# SCH_FC-ESP32_2026-02-12.net
KiCad netlist of a schematic drawn in EasyEDA
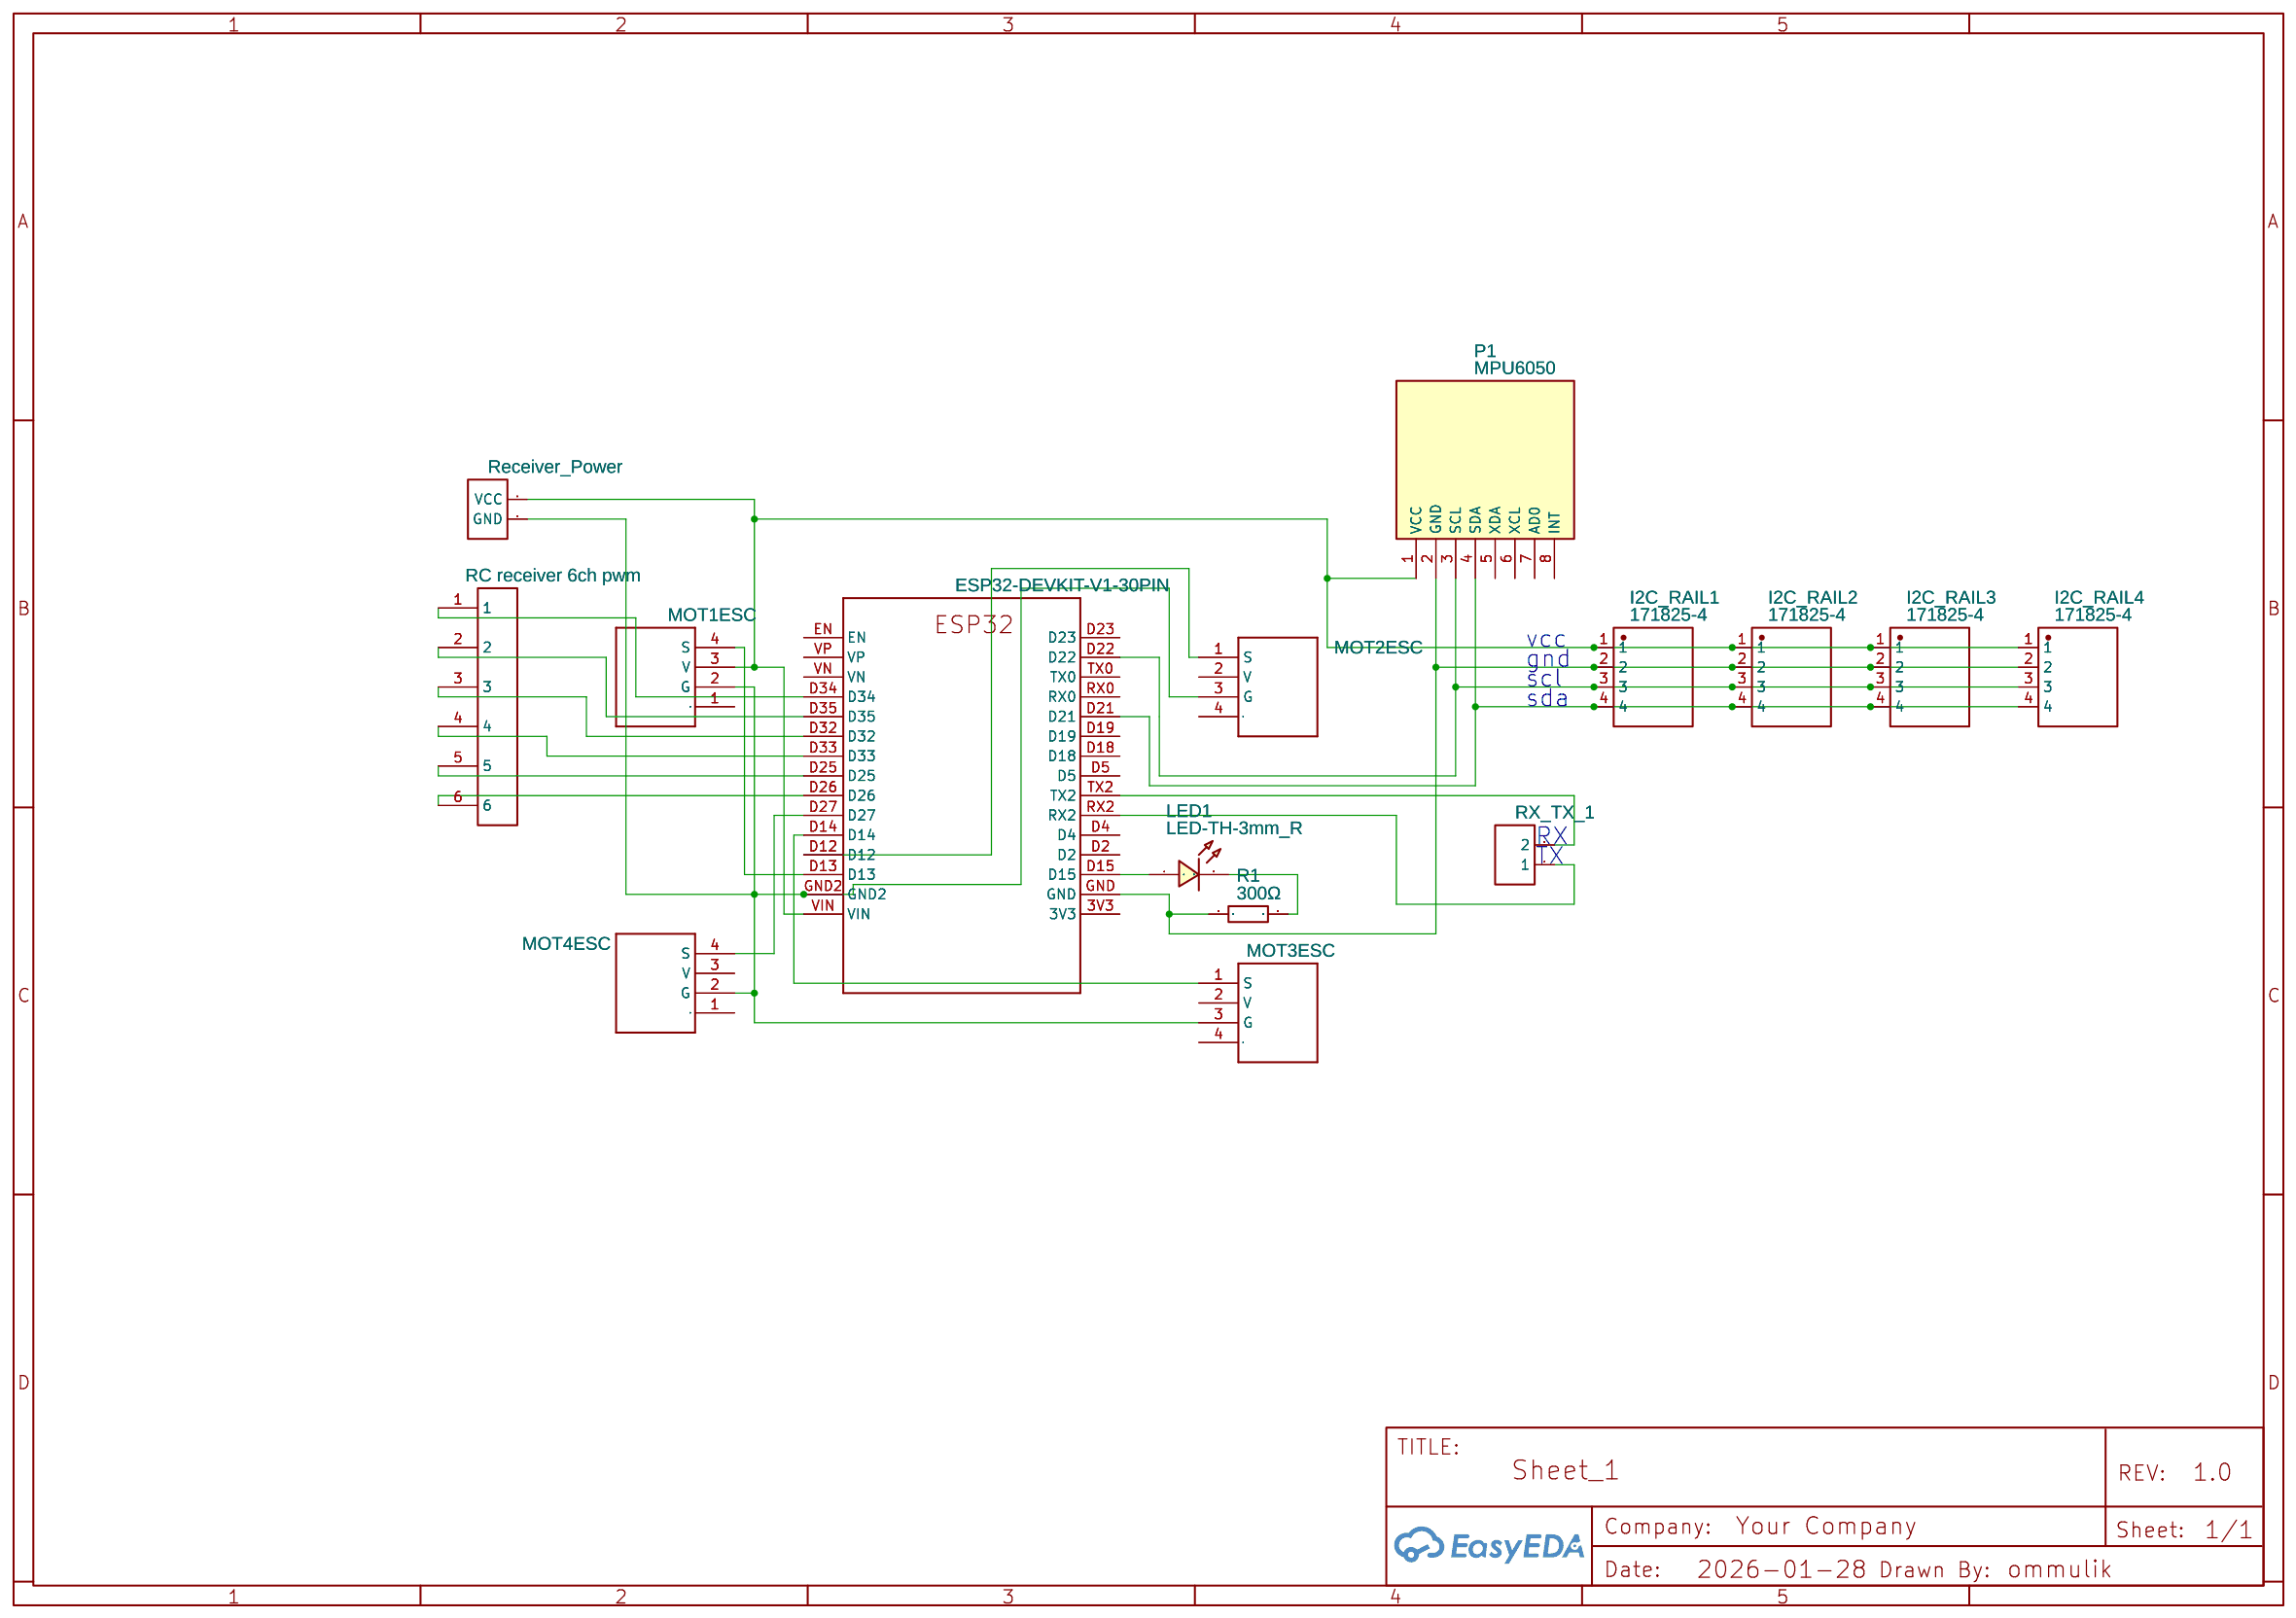
[diagram p0: schematic sheet]

(export (version "E")
  (design (tool "Eeschema 10.0.6"))
  (components
    (comp (ref "2") (value "ESP32-DEVKIT-V1-30PIN") (libsource (lib "") (part "ESP32-DEVKIT-V1-30PIN")))
    (comp (ref "H1") (value "Receiver_Power") (libsource (lib "") (part "HDR-F-2.54_1x2_1")))
    (comp (ref "H2") (value "RX_TX_1") (libsource (lib "") (part "HDR-F-2.54_1x2")))
    (comp (ref "I2C_RAIL1")
      (value "171825-4")
      (fields (field (name "Manufacturer") "TE Connectivity(泰科电子)"))
      (libsource (lib "") (part "171825-4"))
    )
    (comp (ref "I2C_RAIL2")
      (value "171825-4")
      (fields (field (name "Manufacturer") "TE Connectivity(泰科电子)"))
      (libsource (lib "") (part "171825-4"))
    )
    (comp (ref "I2C_RAIL3")
      (value "171825-4")
      (fields (field (name "Manufacturer") "TE Connectivity(泰科电子)"))
      (libsource (lib "") (part "171825-4"))
    )
    (comp (ref "I2C_RAIL4")
      (value "171825-4")
      (fields (field (name "Manufacturer") "TE Connectivity(泰科电子)"))
      (libsource (lib "") (part "171825-4"))
    )
    (comp (ref "J1") (value "MOT4ESC") (libsource (lib "") (part "bluepill_scsi-rescue_171825-4-171825-4")))
    (comp (ref "J2") (value "MOT1ESC") (libsource (lib "") (part "bluepill_scsi-rescue_171825-4-171825-4")))
    (comp (ref "J3") (value "MOT2ESC") (libsource (lib "") (part "bluepill_scsi-rescue_171825-4-171825-4_1")))
    (comp (ref "J4") (value "MOT3ESC") (libsource (lib "") (part "bluepill_scsi-rescue_171825-4-171825-4_1")))
    (comp (ref "LED1")
      (value "LED-TH-3mm_R")
      (fields
        (field (name "Manufacturer Part") "204-10SDRD/S530-A3-L")
        (field (name "Manufacturer") "EVERLIGHT(台湾亿光)")
      )
      (libsource (lib "") (part "LED-TH-3mm_R"))
    )
    (comp (ref "P1") (value "MPU6050") (libsource (lib "") (part "MPU6050")))
    (comp (ref "R1")
      (value "300Ω")
      (fields
        (field (name "Manufacturer Part") "CF1/4W-330KΩ±5% T52")
        (field (name "Manufacturer") "CCO(千志电子)")
      )
      (libsource (lib "") (part "CF1/4W-330KΩ±5% T52"))
    )
    (comp (ref "S2") (value "RC receiver 6ch pwm") (libsource (lib "") (part "6PIN_BERG")))
  )
  (nets
    (net (code "1") (name "Net-(2-PadD15)") (class "Default")
      (node (ref "2") (pin "D15") (pinfunction "D15_D15") (pintype "unspecified"))
      (node (ref "LED1") (pin "1") (pinfunction "1_1") (pintype "unspecified"))
    )
    (net (code "2") (name "Net-(2-PadD25)") (class "Default")
      (node (ref "2") (pin "D25") (pinfunction "D25_D25") (pintype "unspecified"))
      (node (ref "S2") (pin "5") (pinfunction "5_5") (pintype "unspecified"))
    )
    (net (code "3") (name "Net-(2-PadD26)") (class "Default")
      (node (ref "2") (pin "D26") (pinfunction "D26_D26") (pintype "unspecified"))
      (node (ref "S2") (pin "6") (pinfunction "6_6") (pintype "unspecified"))
    )
    (net (code "4") (name "Net-(2-PadD32)") (class "Default")
      (node (ref "2") (pin "D32") (pinfunction "D32_D32") (pintype "unspecified"))
      (node (ref "S2") (pin "3") (pinfunction "3_3") (pintype "unspecified"))
    )
    (net (code "5") (name "Net-(2-PadD33)") (class "Default")
      (node (ref "2") (pin "D33") (pinfunction "D33_D33") (pintype "unspecified"))
      (node (ref "S2") (pin "4") (pinfunction "4_4") (pintype "unspecified"))
    )
    (net (code "6") (name "Net-(2-PadD34)") (class "Default")
      (node (ref "2") (pin "D34") (pinfunction "D34_D34") (pintype "unspecified"))
      (node (ref "S2") (pin "1") (pinfunction "1_1") (pintype "unspecified"))
    )
    (net (code "7") (name "Net-(2-PadD35)") (class "Default")
      (node (ref "2") (pin "D35") (pinfunction "D35_D35") (pintype "unspecified"))
      (node (ref "S2") (pin "2") (pinfunction "2_2") (pintype "unspecified"))
    )
    (net (code "8") (name "Net-(2-PadRX2)") (class "Default")
      (node (ref "2") (pin "RX2") (pinfunction "RX2_RX2") (pintype "unspecified"))
      (node (ref "H2") (pin "1") (pinfunction "1_1") (pintype "input"))
    )
    (net (code "9") (name "Net-(2-PadTX2)") (class "Default")
      (node (ref "2") (pin "TX2") (pinfunction "TX2_TX2") (pintype "unspecified"))
      (node (ref "H2") (pin "2") (pinfunction "2_2") (pintype "input"))
    )
    (net (code "10") (name "Net-(H1-GND)") (class "Default")
      (node (ref "2") (pin "GND2") (pinfunction "GND2_GND2") (pintype "unspecified"))
      (node (ref "H1") (pin "1") (pinfunction "GND_1") (pintype "input"))
      (node (ref "J1") (pin "2") (pinfunction "G_2") (pintype "unspecified"))
      (node (ref "J2") (pin "2") (pinfunction "G_2") (pintype "unspecified"))
      (node (ref "J3") (pin "3") (pinfunction "G_3") (pintype "unspecified"))
      (node (ref "J4") (pin "3") (pinfunction "G_3") (pintype "unspecified"))
    )
    (net (code "11") (name "Net-(H1-VCC)") (class "Default")
      (node (ref "2") (pin "VIN") (pinfunction "VIN_VIN") (pintype "unspecified"))
      (node (ref "H1") (pin "2") (pinfunction "VCC_2") (pintype "input"))
      (node (ref "I2C_RAIL1") (pin "1") (pinfunction "1_1") (pintype "unspecified"))
      (node (ref "I2C_RAIL2") (pin "1") (pinfunction "1_1") (pintype "unspecified"))
      (node (ref "I2C_RAIL3") (pin "1") (pinfunction "1_1") (pintype "unspecified"))
      (node (ref "I2C_RAIL4") (pin "1") (pinfunction "1_1") (pintype "unspecified"))
      (node (ref "J2") (pin "3") (pinfunction "V_3") (pintype "unspecified"))
      (node (ref "P1") (pin "1") (pinfunction "VCC_1") (pintype "unspecified"))
    )
    (net (code "12") (name "Net-(J1-S)") (class "Default")
      (node (ref "2") (pin "D27") (pinfunction "D27_D27") (pintype "unspecified"))
      (node (ref "J1") (pin "4") (pinfunction "S_4") (pintype "unspecified"))
    )
    (net (code "13") (name "Net-(J2-S)") (class "Default")
      (node (ref "2") (pin "D13") (pinfunction "D13_D13") (pintype "unspecified"))
      (node (ref "J2") (pin "4") (pinfunction "S_4") (pintype "unspecified"))
    )
    (net (code "14") (name "Net-(J3-S)") (class "Default")
      (node (ref "2") (pin "D12") (pinfunction "D12_D12") (pintype "unspecified"))
      (node (ref "J3") (pin "1") (pinfunction "S_1") (pintype "unspecified"))
    )
    (net (code "15") (name "Net-(J4-S)") (class "Default")
      (node (ref "2") (pin "D14") (pinfunction "D14_D14") (pintype "unspecified"))
      (node (ref "J4") (pin "1") (pinfunction "S_1") (pintype "unspecified"))
    )
    (net (code "16") (name "Net-(LED1-Pad2)") (class "Default")
      (node (ref "LED1") (pin "2") (pinfunction "2_2") (pintype "unspecified"))
      (node (ref "R1") (pin "1") (pinfunction "1_1") (pintype "unspecified"))
    )
    (net (code "17") (name "Net-(P1-GND)") (class "Default")
      (node (ref "2") (pin "GND") (pinfunction "GND_GND") (pintype "unspecified"))
      (node (ref "I2C_RAIL1") (pin "2") (pinfunction "2_2") (pintype "unspecified"))
      (node (ref "I2C_RAIL2") (pin "2") (pinfunction "2_2") (pintype "unspecified"))
      (node (ref "I2C_RAIL3") (pin "2") (pinfunction "2_2") (pintype "unspecified"))
      (node (ref "I2C_RAIL4") (pin "2") (pinfunction "2_2") (pintype "unspecified"))
      (node (ref "P1") (pin "2") (pinfunction "GND_2") (pintype "unspecified"))
      (node (ref "R1") (pin "2") (pinfunction "2_2") (pintype "unspecified"))
    )
    (net (code "18") (name "Net-(P1-SCL)") (class "Default")
      (node (ref "2") (pin "D22") (pinfunction "D22_D22") (pintype "unspecified"))
      (node (ref "I2C_RAIL1") (pin "3") (pinfunction "3_3") (pintype "unspecified"))
      (node (ref "I2C_RAIL2") (pin "3") (pinfunction "3_3") (pintype "unspecified"))
      (node (ref "I2C_RAIL3") (pin "3") (pinfunction "3_3") (pintype "unspecified"))
      (node (ref "I2C_RAIL4") (pin "3") (pinfunction "3_3") (pintype "unspecified"))
      (node (ref "P1") (pin "3") (pinfunction "SCL_3") (pintype "unspecified"))
    )
    (net (code "19") (name "Net-(P1-SDA)") (class "Default")
      (node (ref "2") (pin "D21") (pinfunction "D21_D21") (pintype "unspecified"))
      (node (ref "I2C_RAIL1") (pin "4") (pinfunction "4_4") (pintype "unspecified"))
      (node (ref "I2C_RAIL2") (pin "4") (pinfunction "4_4") (pintype "unspecified"))
      (node (ref "I2C_RAIL3") (pin "4") (pinfunction "4_4") (pintype "unspecified"))
      (node (ref "I2C_RAIL4") (pin "4") (pinfunction "4_4") (pintype "unspecified"))
      (node (ref "P1") (pin "4") (pinfunction "SDA_4") (pintype "unspecified"))
    )
    (net (code "20") (name "unconnected-(2-Pad3V3)") (class "Default")
      (node (ref "2") (pin "3V3") (pinfunction "3V3_3V3") (pintype "unspecified"))
    )
    (net (code "21") (name "unconnected-(2-PadD2)") (class "Default")
      (node (ref "2") (pin "D2") (pinfunction "D2_D2") (pintype "unspecified"))
    )
    (net (code "22") (name "unconnected-(2-PadD4)") (class "Default")
      (node (ref "2") (pin "D4") (pinfunction "D4_D4") (pintype "unspecified"))
    )
    (net (code "23") (name "unconnected-(2-PadD5)") (class "Default")
      (node (ref "2") (pin "D5") (pinfunction "D5_D5") (pintype "unspecified"))
    )
    (net (code "24") (name "unconnected-(2-PadD18)") (class "Default")
      (node (ref "2") (pin "D18") (pinfunction "D18_D18") (pintype "unspecified"))
    )
    (net (code "25") (name "unconnected-(2-PadD19)") (class "Default")
      (node (ref "2") (pin "D19") (pinfunction "D19_D19") (pintype "unspecified"))
    )
    (net (code "26") (name "unconnected-(2-PadD23)") (class "Default")
      (node (ref "2") (pin "D23") (pinfunction "D23_D23") (pintype "unspecified"))
    )
    (net (code "27") (name "unconnected-(2-PadEN)") (class "Default")
      (node (ref "2") (pin "EN") (pinfunction "EN_EN") (pintype "unspecified"))
    )
    (net (code "28") (name "unconnected-(2-PadRX0)") (class "Default")
      (node (ref "2") (pin "RX0") (pinfunction "RX0_RX0") (pintype "unspecified"))
    )
    (net (code "29") (name "unconnected-(2-PadTX0)") (class "Default")
      (node (ref "2") (pin "TX0") (pinfunction "TX0_TX0") (pintype "unspecified"))
    )
    (net (code "30") (name "unconnected-(2-PadVN)") (class "Default")
      (node (ref "2") (pin "VN") (pinfunction "VN_VN") (pintype "unspecified"))
    )
    (net (code "31") (name "unconnected-(2-PadVP)") (class "Default")
      (node (ref "2") (pin "VP") (pinfunction "VP_VP") (pintype "unspecified"))
    )
    (net (code "32") (name "unconnected-(J1-Pad1)") (class "Default")
      (node (ref "J1") (pin "1") (pinfunction "1_1") (pintype "unspecified"))
    )
    (net (code "33") (name "unconnected-(J1-V-Pad3)") (class "Default")
      (node (ref "J1") (pin "3") (pinfunction "V_3") (pintype "unspecified"))
    )
    (net (code "34") (name "unconnected-(J2-Pad1)") (class "Default")
      (node (ref "J2") (pin "1") (pinfunction "1_1") (pintype "unspecified"))
    )
    (net (code "35") (name "unconnected-(J3-Pad4)") (class "Default")
      (node (ref "J3") (pin "4") (pinfunction "4_4") (pintype "unspecified"))
    )
    (net (code "36") (name "unconnected-(J3-V-Pad2)") (class "Default")
      (node (ref "J3") (pin "2") (pinfunction "V_2") (pintype "unspecified"))
    )
    (net (code "37") (name "unconnected-(J4-Pad4)") (class "Default")
      (node (ref "J4") (pin "4") (pinfunction "4_4") (pintype "unspecified"))
    )
    (net (code "38") (name "unconnected-(J4-V-Pad2)") (class "Default")
      (node (ref "J4") (pin "2") (pinfunction "V_2") (pintype "unspecified"))
    )
    (net (code "39") (name "unconnected-(P1-AD0-Pad7)") (class "Default")
      (node (ref "P1") (pin "7") (pinfunction "AD0_7") (pintype "unspecified"))
    )
    (net (code "40") (name "unconnected-(P1-INT-Pad8)") (class "Default")
      (node (ref "P1") (pin "8") (pinfunction "INT_8") (pintype "unspecified"))
    )
    (net (code "41") (name "unconnected-(P1-XCL-Pad6)") (class "Default")
      (node (ref "P1") (pin "6") (pinfunction "XCL_6") (pintype "unspecified"))
    )
    (net (code "42") (name "unconnected-(P1-XDA-Pad5)") (class "Default")
      (node (ref "P1") (pin "5") (pinfunction "XDA_5") (pintype "unspecified"))
    )
  )
)
